# Cell3_Balancing.net
KiCad netlist of a schematic drawn in Altium Designer
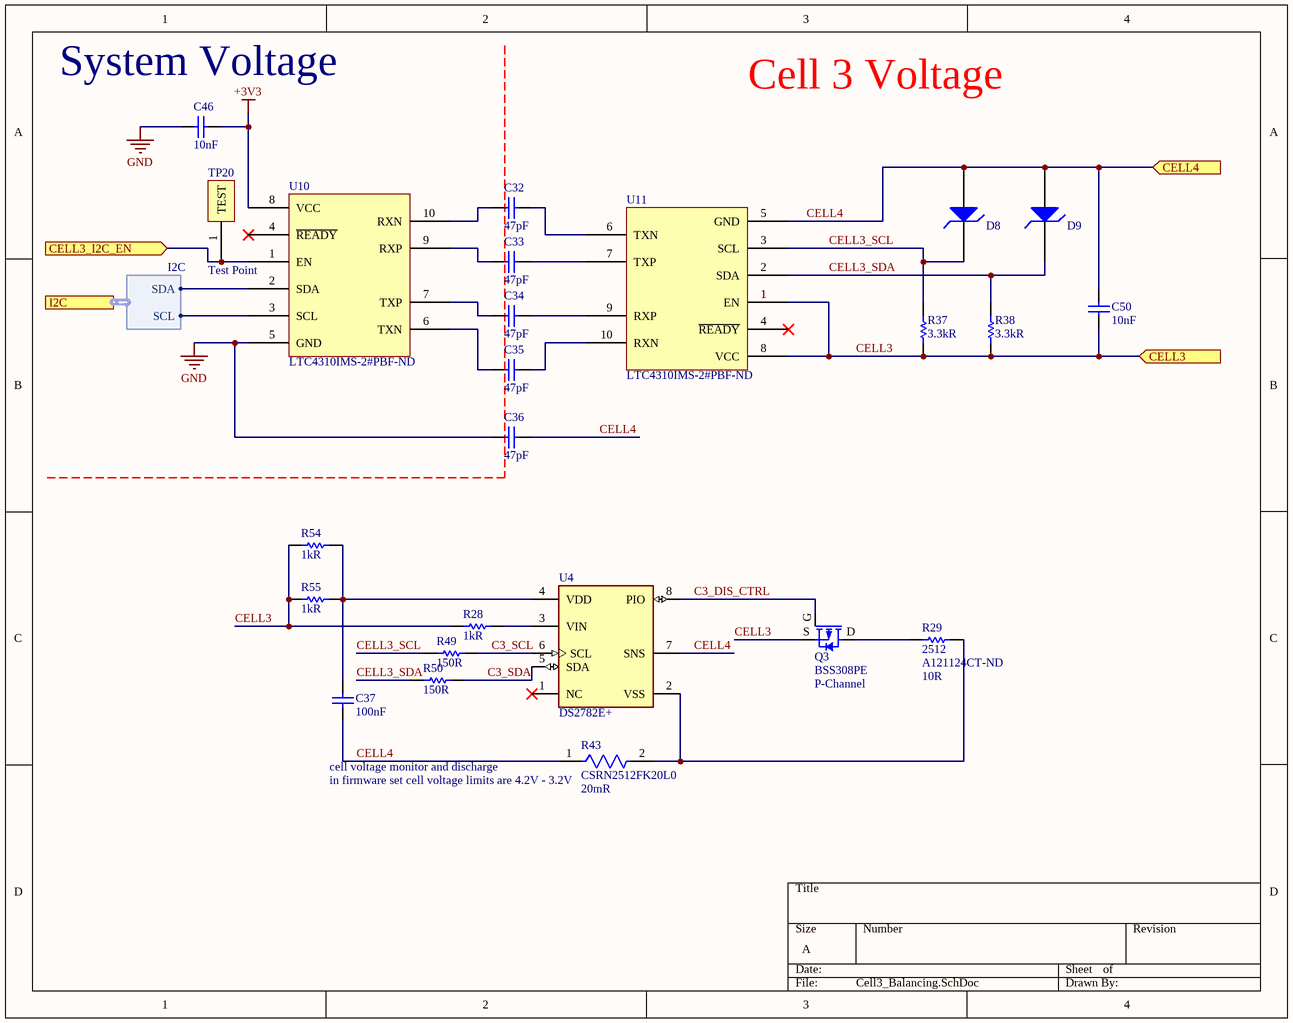
[diagram p0: Cell3_Balancing.SchDoc]

(export (version "E")
  (design (tool "Eeschema 10.0.6"))
  (components
    (comp (ref "C32")
      (value "06031A470FAT2A")
      (footprint "CAPC1608X90X35ML15T15")
      (fields (field (name "MANUFACTURER") "AVX Interconnect / Elco") (field (name "CAPACITANCE") "47pF"))
      (libsource (lib "Altium Content Vault") (part "CAP"))
    )
    (comp (ref "C33")
      (value "06031A470FAT2A")
      (footprint "CAPC1608X90X35ML15T15")
      (fields (field (name "MANUFACTURER") "AVX Interconnect / Elco") (field (name "CAPACITANCE") "47pF"))
      (libsource (lib "Altium Content Vault") (part "CAP"))
    )
    (comp (ref "C34")
      (value "06031A470FAT2A")
      (footprint "CAPC1608X90X35ML15T15")
      (fields (field (name "MANUFACTURER") "AVX Interconnect / Elco") (field (name "CAPACITANCE") "47pF"))
      (libsource (lib "Altium Content Vault") (part "CAP"))
    )
    (comp (ref "C35")
      (value "06031A470FAT2A")
      (footprint "CAPC1608X90X35ML15T15")
      (fields (field (name "MANUFACTURER") "AVX Interconnect / Elco") (field (name "CAPACITANCE") "47pF"))
      (libsource (lib "Altium Content Vault") (part "CAP"))
    )
    (comp (ref "C36")
      (value "06031A470FAT2A")
      (footprint "CAPC1608X90X35ML15T15")
      (fields (field (name "MANUFACTURER") "AVX Interconnect / Elco") (field (name "CAPACITANCE") "47pF"))
      (libsource (lib "Altium Content Vault") (part "CAP"))
    )
    (comp (ref "C37")
      (value "Capacitor 0402")
      (footprint "C0402")
      (description "CAP CER 0.1UF 25V X5R 0402 / High Value Multilayer Ceramic Capacitors (High dielectric type)")
      (fields
        (field (name "MANUFACTURER") "Taiyo Yuden")
        (field (name "MANUFACTURER PART NUMBER") "TMK105BJ104KV-F")
        (field (name "CAPACITANCE") "100nF")
      )
      (libsource (lib "Wally_BMS") (part "Capacitor 0402"))
    )
    (comp (ref "C46")
      (value "Capacitor 0402")
      (footprint "C0402")
      (description "Cap Ceramic 0.01uF 25V X7R 10% Pad SMD 0402 125C T/R")
      (fields
        (field (name "MANUFACTURER") "Samsung")
        (field (name "MANUFACTURER PART NUMBER") "CL05B103KA5NNNC")
        (field (name "CAPACITANCE") "10nF")
      )
      (libsource (lib "Wally_BMS") (part "Capacitor 0402"))
    )
    (comp (ref "C50")
      (value "Capacitor 0402")
      (footprint "C0402")
      (description "Cap Ceramic 0.01uF 25V X7R 10% Pad SMD 0402 125C T/R")
      (fields
        (field (name "MANUFACTURER") "Samsung")
        (field (name "MANUFACTURER PART NUMBER") "CL05B103KA5NNNC")
        (field (name "CAPACITANCE") "10nF")
      )
      (libsource (lib "Wally_BMS") (part "Capacitor 0402"))
    )
    (comp (ref "D8")
      (value "BZT52C4V7LP-7")
      (footprint "bzt52c4v7lp-7")
      (description "BZT52C4V7LP Series 4.7 V 10 mA Surface Mount Zener Diode - DFN1006-2")
      (fields (field (name "MANUFACTURER") "Diodes") (field (name "TOLERANCE") "6%"))
      (libsource (lib "Wally_BMS") (part "BZT52C4V7LP-7"))
    )
    (comp (ref "D9")
      (value "BZT52C4V7LP-7")
      (footprint "bzt52c4v7lp-7")
      (description "BZT52C4V7LP Series 4.7 V 10 mA Surface Mount Zener Diode - DFN1006-2")
      (fields (field (name "MANUFACTURER") "Diodes") (field (name "TOLERANCE") "6%"))
      (libsource (lib "Wally_BMS") (part "BZT52C4V7LP-7"))
    )
    (comp (ref "Q3")
      (value "BSS308PE")
      (footprint "BSS308PE")
      (description "MOSFET P-CH 30V 2A SOT23")
      (fields (field (name "FET TYPE") "P-Channel"))
      (libsource (lib "Transistors") (part "BSS308PE"))
    )
    (comp (ref "R28")
      (value "Resistor 0402")
      (footprint "RES0402")
      (description "Res Thick Film 0402 1K Ohm 1% 0.063W(1/16W) ±100ppm/C Pad SMD Automotive T/R")
      (fields
        (field (name "MANUFACTURER") "Stackpole Electronics")
        (field (name "MANUFACTURER PART NUMBER") "RMCF0402FT1K00")
        (field (name "RESISTANCE") "1kR")
      )
      (libsource (lib "Wally_BMS") (part "Resistor 0402"))
    )
    (comp (ref "R29")
      (value "Resistor 2512")
      (footprint "RES2512")
      (fields
        (field (name "PACKAGE / CASE") "2512")
        (field (name "SUPPLIER PART NUMBER 1") "A121124CT-ND")
        (field (name "MANUFACTURER") "TE Connectivity CGS")
        (field (name "MANUFACTURER PART NUMBER") "1-2176230-4")
        (field (name "RESISTANCE") "10R")
        (field (name "TOLERANCE") "5%")
      )
      (libsource (lib "Wally_BMS") (part "Resistor 2512"))
    )
    (comp (ref "R37")
      (value "Resistor 0402")
      (footprint "RES0402")
      (description "Res Thin Film 0402 3.3K Ohm 1% 1/16W ±50ppm/°C Molded SMD SMD Paper T/R")
      (fields
        (field (name "MANUFACTURER") "Yageo")
        (field (name "MANUFACTURER PART NUMBER") "RT0402FRE073K3L")
        (field (name "RESISTANCE") "3.3kR")
      )
      (libsource (lib "Wally_BMS") (part "Resistor 0402"))
    )
    (comp (ref "R38")
      (value "Resistor 0402")
      (footprint "RES0402")
      (description "Res Thin Film 0402 3.3K Ohm 1% 1/16W ±50ppm/°C Molded SMD SMD Paper T/R")
      (fields
        (field (name "MANUFACTURER") "Yageo")
        (field (name "MANUFACTURER PART NUMBER") "RT0402FRE073K3L")
        (field (name "RESISTANCE") "3.3kR")
      )
      (libsource (lib "Wally_BMS") (part "Resistor 0402"))
    )
    (comp (ref "R43")
      (value "CSRN2512FK20L0")
      (footprint "FP-CSRN2512-IPC_C")
      (description "Res Thick Film 2512 20mΩ 1% 2W ±200ppm/°C Molded SMD Plastic T/R")
      (fields (field (name "RESISTANCE") "20mR") (field (name "TOLERANCE") "1%"))
      (libsource (lib "Altium Content Vault") (part "1029c3af85768c4190bb7ad29bc67b5"))
    )
    (comp (ref "R49")
      (value "Resistor 0402")
      (footprint "RES0402")
      (description "Res Thin Film 0402 150 Ohm 1% 1/16W ±50ppm/°C Molded SMD SMD Paper T/R")
      (fields
        (field (name "MANUFACTURER") "Yageo")
        (field (name "MANUFACTURER PART NUMBER") "RT0402FRE07150RL")
        (field (name "RESISTANCE") "150R")
      )
      (libsource (lib "Wally_BMS") (part "Resistor 0402"))
    )
    (comp (ref "R50")
      (value "Resistor 0402")
      (footprint "RES0402")
      (description "Res Thin Film 0402 150 Ohm 1% 1/16W ±50ppm/°C Molded SMD SMD Paper T/R")
      (fields
        (field (name "MANUFACTURER") "Yageo")
        (field (name "MANUFACTURER PART NUMBER") "RT0402FRE07150RL")
        (field (name "RESISTANCE") "150R")
      )
      (libsource (lib "Wally_BMS") (part "Resistor 0402"))
    )
    (comp (ref "R54")
      (value "Resistor 0402")
      (footprint "RES0402")
      (description "Res Thick Film 0402 1K Ohm 1% 0.063W(1/16W) ±100ppm/C Pad SMD Automotive T/R")
      (fields
        (field (name "MANUFACTURER") "Stackpole Electronics")
        (field (name "MANUFACTURER PART NUMBER") "RMCF0402FT1K00")
        (field (name "RESISTANCE") "1kR")
      )
      (libsource (lib "Wally_BMS") (part "Resistor 0402"))
    )
    (comp (ref "R55")
      (value "Resistor 0402")
      (footprint "RES0402")
      (description "Res Thick Film 0402 1K Ohm 1% 0.063W(1/16W) ±100ppm/C Pad SMD Automotive T/R")
      (fields
        (field (name "MANUFACTURER") "Stackpole Electronics")
        (field (name "MANUFACTURER PART NUMBER") "RMCF0402FT1K00")
        (field (name "RESISTANCE") "1kR")
      )
      (libsource (lib "Wally_BMS") (part "Resistor 0402"))
    )
    (comp (ref "TP20")
      (value "Test Point")
      (footprint "TEST POINT")
      (libsource (lib "Wally_BMS") (part "Test Point"))
    )
    (comp (ref "U4")
      (value "DS2782E+")
      (footprint "FP-H8-2-MFG")
      (description "IC FUEL GAUGE BATT 8TSSOP")
      (fields
        (field (name "OCTOPART") "https://octopart.com/ds2782e%2B-maxim+integrated-8045252")
        (field (name "MANUFACTURER") "Maxim")
      )
      (libsource (lib "Altium Content Vault") (part "f9098ddd067e7739cd521d50be25c58"))
    )
    (comp (ref "U10")
      (value "LTC4310IMS-2#PBF-ND")
      (footprint "MSOP-10_MS_LIT")
      (description "DIGITAL ISOLATOR 2CH I2C 10MSOP")
      (libsource (lib "") (part "LTC4310IMS-2#PBF_1"))
    )
    (comp (ref "U11")
      (value "LTC4310IMS-2#PBF-ND")
      (footprint "MSOP-10_MS_LIT")
      (description "DIGITAL ISOLATOR 2CH I2C 10MSOP")
      (libsource (lib "Wally_BMS") (part "LTC4310IMS-2#PBF"))
    )
  )
  (nets
    (net (code "2") (name "+3V3") (class "Default")
      (node (ref "C46") (pin "1") (pinfunction "1_1") (pintype "passive"))
      (node (ref "U10") (pin "8") (pinfunction "VCC_8") (pintype "passive"))
    )
    (net (code "3") (name "/C3_DIS_CTRL") (class "Default")
      (node (ref "Q3") (pin "G") (pinfunction "G_G") (pintype "passive"))
      (node (ref "U4") (pin "8") (pinfunction "PIO_8") (pintype "bidirectional"))
    )
    (net (code "4") (name "/C3_SCL") (class "Default")
      (node (ref "R49") (pin "1") (pinfunction "1_1") (pintype "passive"))
      (node (ref "U4") (pin "6") (pinfunction "SCL_6") (pintype "input"))
    )
    (net (code "5") (name "/C3_SDA") (class "Default")
      (node (ref "R50") (pin "1") (pinfunction "1_1") (pintype "passive"))
      (node (ref "U4") (pin "5") (pinfunction "SDA_5") (pintype "bidirectional"))
    )
    (net (code "6") (name "/CELL3") (class "Default")
      (node (ref "C50") (pin "2") (pinfunction "2_2") (pintype "passive"))
      (node (ref "Q3") (pin "S") (pinfunction "3_S") (pintype "passive"))
      (node (ref "R28") (pin "1") (pinfunction "1_1") (pintype "passive"))
      (node (ref "R37") (pin "1") (pinfunction "1_1") (pintype "passive"))
      (node (ref "R38") (pin "1") (pinfunction "1_1") (pintype "passive"))
      (node (ref "R54") (pin "1") (pinfunction "1_1") (pintype "passive"))
      (node (ref "R55") (pin "1") (pinfunction "1_1") (pintype "passive"))
      (node (ref "U11") (pin "1") (pinfunction "EN_1") (pintype "passive"))
      (node (ref "U11") (pin "8") (pinfunction "VCC_8") (pintype "passive"))
    )
    (net (code "7") (name "/CELL3_I2C_EN") (class "Default")
      (node (ref "TP20") (pin "1") (pinfunction "TEST_1") (pintype "passive"))
      (node (ref "U10") (pin "1") (pinfunction "EN_1") (pintype "passive"))
    )
    (net (code "8") (name "/CELL3_SCL") (class "Default")
      (node (ref "D8") (pin "1") (pinfunction "K_1") (pintype "passive"))
      (node (ref "R37") (pin "2") (pinfunction "2_2") (pintype "passive"))
      (node (ref "R49") (pin "2") (pinfunction "2_2") (pintype "passive"))
      (node (ref "U11") (pin "3") (pinfunction "SCL_3") (pintype "passive"))
    )
    (net (code "9") (name "/CELL3_SDA") (class "Default")
      (node (ref "D9") (pin "1") (pinfunction "K_1") (pintype "passive"))
      (node (ref "R38") (pin "2") (pinfunction "2_2") (pintype "passive"))
      (node (ref "R50") (pin "2") (pinfunction "2_2") (pintype "passive"))
      (node (ref "U11") (pin "2") (pinfunction "SDA_2") (pintype "passive"))
    )
    (net (code "10") (name "/CELL4") (class "Default")
      (node (ref "C36") (pin "2") (pinfunction "2_2") (pintype "passive"))
      (node (ref "C37") (pin "1") (pinfunction "1_1") (pintype "passive"))
      (node (ref "C50") (pin "1") (pinfunction "1_1") (pintype "passive"))
      (node (ref "D8") (pin "2") (pinfunction "A_2") (pintype "passive"))
      (node (ref "D9") (pin "2") (pinfunction "A_2") (pintype "passive"))
      (node (ref "R43") (pin "1") (pinfunction "1_1") (pintype "passive"))
      (node (ref "U11") (pin "5") (pinfunction "GND_5") (pintype "passive"))
      (node (ref "U4") (pin "7") (pinfunction "SNS_7") (pintype "passive"))
    )
    (net (code "11") (name "/SCL") (class "Default")
      (node (ref "U10") (pin "3") (pinfunction "SCL_3") (pintype "passive"))
    )
    (net (code "12") (name "/SDA") (class "Default")
      (node (ref "U10") (pin "2") (pinfunction "SDA_2") (pintype "passive"))
    )
    (net (code "14") (name "GND") (class "Default")
      (node (ref "C36") (pin "1") (pinfunction "1_1") (pintype "passive"))
      (node (ref "C46") (pin "2") (pinfunction "2_2") (pintype "passive"))
      (node (ref "U10") (pin "5") (pinfunction "GND_5") (pintype "passive"))
    )
    (net (code "15") (name "Net-(Q3-PadD)") (class "Default")
      (node (ref "Q3") (pin "D") (pinfunction "D_D") (pintype "passive"))
      (node (ref "R29") (pin "1") (pinfunction "1_1") (pintype "passive"))
    )
    (net (code "16") (name "Net-(U4-VDD)") (class "Default")
      (node (ref "C37") (pin "2") (pinfunction "2_2") (pintype "passive"))
      (node (ref "R54") (pin "2") (pinfunction "2_2") (pintype "passive"))
      (node (ref "R55") (pin "2") (pinfunction "2_2") (pintype "passive"))
      (node (ref "U4") (pin "4") (pinfunction "VDD_4") (pintype "power_in"))
    )
    (net (code "17") (name "Net-(U4-VIN)") (class "Default")
      (node (ref "R28") (pin "2") (pinfunction "2_2") (pintype "passive"))
      (node (ref "U4") (pin "3") (pinfunction "VIN_3") (pintype "passive"))
    )
    (net (code "18") (name "Net-(U4-VSS)") (class "Default")
      (node (ref "R29") (pin "2") (pinfunction "2_2") (pintype "passive"))
      (node (ref "R43") (pin "2") (pinfunction "2_2") (pintype "passive"))
      (node (ref "U4") (pin "2") (pinfunction "VSS_2") (pintype "power_in"))
    )
    (net (code "19") (name "Net-(U10-RXN)") (class "Default")
      (node (ref "C32") (pin "1") (pinfunction "1_1") (pintype "passive"))
      (node (ref "U10") (pin "10") (pinfunction "RXN_10") (pintype "passive"))
    )
    (net (code "20") (name "Net-(U10-RXP)") (class "Default")
      (node (ref "C33") (pin "1") (pinfunction "1_1") (pintype "passive"))
      (node (ref "U10") (pin "9") (pinfunction "RXP_9") (pintype "passive"))
    )
    (net (code "21") (name "Net-(U10-TXN)") (class "Default")
      (node (ref "C35") (pin "1") (pinfunction "1_1") (pintype "passive"))
      (node (ref "U10") (pin "6") (pinfunction "TXN_6") (pintype "passive"))
    )
    (net (code "22") (name "Net-(U10-TXP)") (class "Default")
      (node (ref "C34") (pin "1") (pinfunction "1_1") (pintype "passive"))
      (node (ref "U10") (pin "7") (pinfunction "TXP_7") (pintype "passive"))
    )
    (net (code "23") (name "Net-(U11-RXN)") (class "Default")
      (node (ref "C35") (pin "2") (pinfunction "2_2") (pintype "passive"))
      (node (ref "U11") (pin "10") (pinfunction "RXN_10") (pintype "passive"))
    )
    (net (code "24") (name "Net-(U11-RXP)") (class "Default")
      (node (ref "C34") (pin "2") (pinfunction "2_2") (pintype "passive"))
      (node (ref "U11") (pin "9") (pinfunction "RXP_9") (pintype "passive"))
    )
    (net (code "25") (name "Net-(U11-TXN)") (class "Default")
      (node (ref "C32") (pin "2") (pinfunction "2_2") (pintype "passive"))
      (node (ref "U11") (pin "6") (pinfunction "TXN_6") (pintype "passive"))
    )
    (net (code "26") (name "Net-(U11-TXP)") (class "Default")
      (node (ref "C33") (pin "2") (pinfunction "2_2") (pintype "passive"))
      (node (ref "U11") (pin "7") (pinfunction "TXP_7") (pintype "passive"))
    )
    (net (code "27") (name "unconnected-(U4-NC-Pad1)") (class "Default")
      (node (ref "U4") (pin "1") (pinfunction "NC_1") (pintype "passive+no_connect"))
    )
    (net (code "28") (name "unconnected-(U10-~{READY}-Pad4)") (class "Default")
      (node (ref "U10") (pin "4") (pinfunction "~{READY}_4") (pintype "passive+no_connect"))
    )
    (net (code "29") (name "unconnected-(U11-~{READY}-Pad4)") (class "Default")
      (node (ref "U11") (pin "4") (pinfunction "~{READY}_4") (pintype "passive+no_connect"))
    )
  )
)
